# Input.net
KiCad netlist of a schematic drawn in Altium Designer
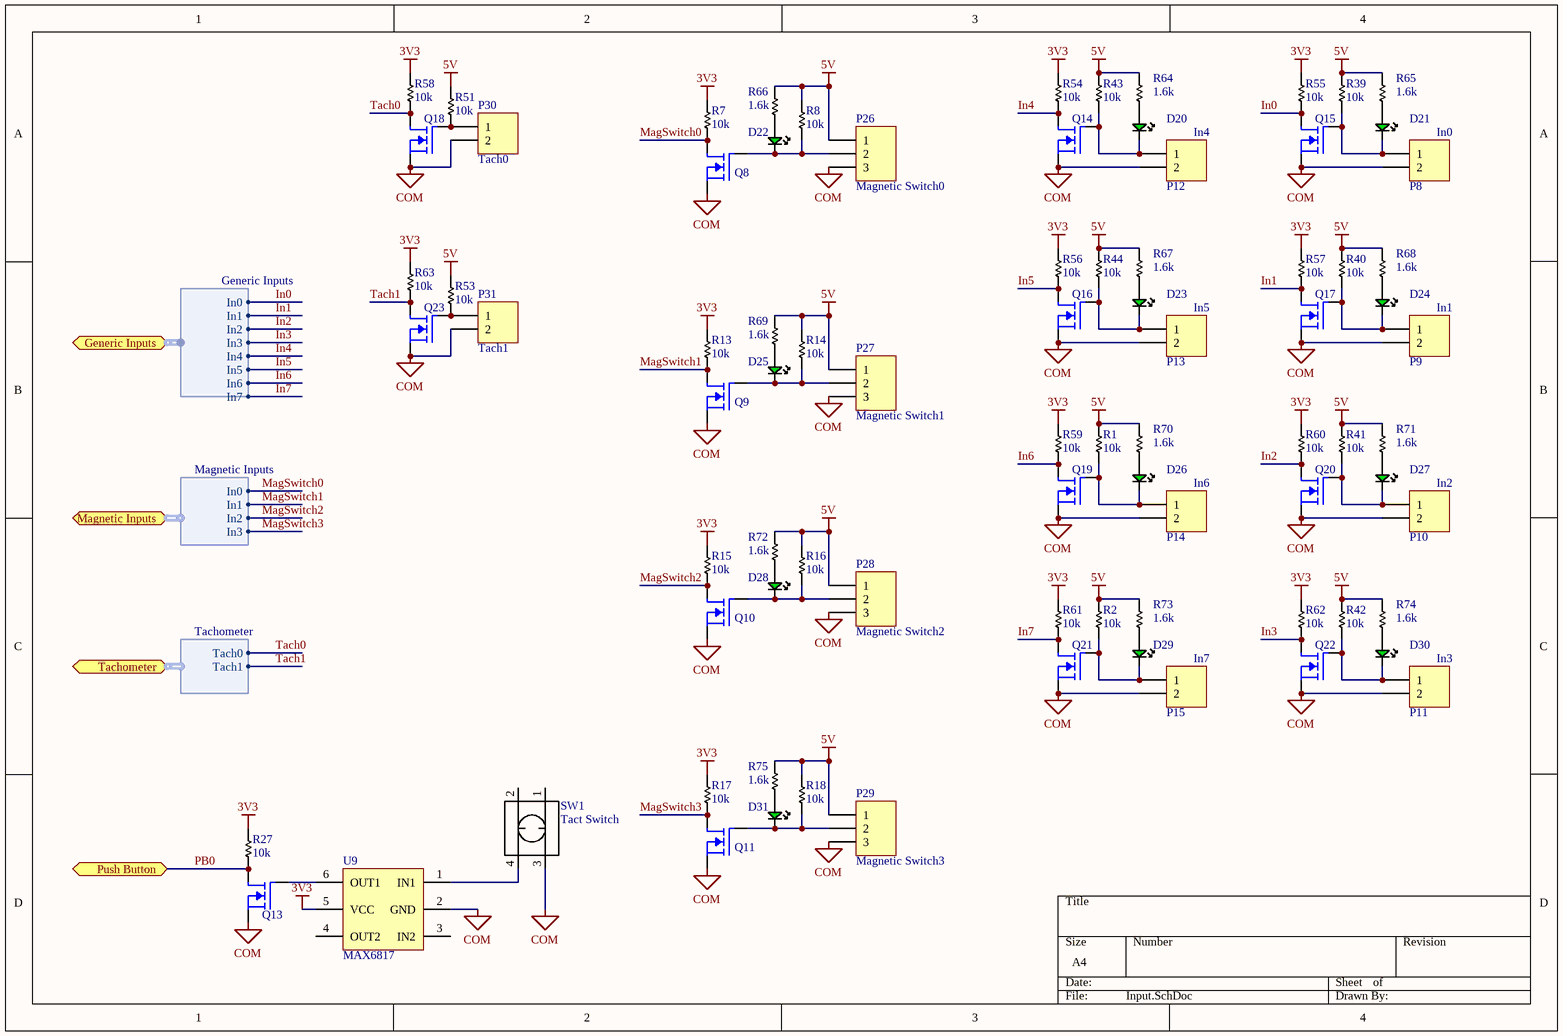
[diagram p0: Input.SchDoc]

(export (version "E")
  (design (tool "Eeschema 10.0.6"))
  (components
    (comp (ref "D20")
      (value "Green")
      (footprint "0603 - Led Green")
      (description "LED SMARTLED GREEN 570NM 0603")
      (fields
        (field (name "PART NUMBER") "LED-Green-2mA-lowBrigthness-0603")
        (field (name "MANUFACTURER") "OSRAM Opto Semiconductor")
        (field (name "CREATED BY") "Pier-Yves")
      )
      (libsource (lib "local") (part "Led Green"))
    )
    (comp (ref "D21")
      (value "Green")
      (footprint "0603 - Led Green")
      (description "LED SMARTLED GREEN 570NM 0603")
      (fields
        (field (name "PART NUMBER") "LED-Green-2mA-lowBrigthness-0603")
        (field (name "MANUFACTURER") "OSRAM Opto Semiconductor")
        (field (name "CREATED BY") "Pier-Yves")
      )
      (libsource (lib "local") (part "Led Green"))
    )
    (comp (ref "D22")
      (value "Green")
      (footprint "0603 - Led Green")
      (description "LED SMARTLED GREEN 570NM 0603")
      (fields
        (field (name "PART NUMBER") "LED-Green-2mA-lowBrigthness-0603")
        (field (name "MANUFACTURER") "OSRAM Opto Semiconductor")
        (field (name "CREATED BY") "Pier-Yves")
      )
      (libsource (lib "local") (part "Led Green"))
    )
    (comp (ref "D23")
      (value "Green")
      (footprint "0603 - Led Green")
      (description "LED SMARTLED GREEN 570NM 0603")
      (fields
        (field (name "PART NUMBER") "LED-Green-2mA-lowBrigthness-0603")
        (field (name "MANUFACTURER") "OSRAM Opto Semiconductor")
        (field (name "CREATED BY") "Pier-Yves")
      )
      (libsource (lib "local") (part "Led Green"))
    )
    (comp (ref "D24")
      (value "Green")
      (footprint "0603 - Led Green")
      (description "LED SMARTLED GREEN 570NM 0603")
      (fields
        (field (name "PART NUMBER") "LED-Green-2mA-lowBrigthness-0603")
        (field (name "MANUFACTURER") "OSRAM Opto Semiconductor")
        (field (name "CREATED BY") "Pier-Yves")
      )
      (libsource (lib "local") (part "Led Green"))
    )
    (comp (ref "D25")
      (value "Green")
      (footprint "0603 - Led Green")
      (description "LED SMARTLED GREEN 570NM 0603")
      (fields
        (field (name "PART NUMBER") "LED-Green-2mA-lowBrigthness-0603")
        (field (name "MANUFACTURER") "OSRAM Opto Semiconductor")
        (field (name "CREATED BY") "Pier-Yves")
      )
      (libsource (lib "local") (part "Led Green"))
    )
    (comp (ref "D26")
      (value "Green")
      (footprint "0603 - Led Green")
      (description "LED SMARTLED GREEN 570NM 0603")
      (fields
        (field (name "PART NUMBER") "LED-Green-2mA-lowBrigthness-0603")
        (field (name "MANUFACTURER") "OSRAM Opto Semiconductor")
        (field (name "CREATED BY") "Pier-Yves")
      )
      (libsource (lib "local") (part "Led Green"))
    )
    (comp (ref "D27")
      (value "Green")
      (footprint "0603 - Led Green")
      (description "LED SMARTLED GREEN 570NM 0603")
      (fields
        (field (name "PART NUMBER") "LED-Green-2mA-lowBrigthness-0603")
        (field (name "MANUFACTURER") "OSRAM Opto Semiconductor")
        (field (name "CREATED BY") "Pier-Yves")
      )
      (libsource (lib "local") (part "Led Green"))
    )
    (comp (ref "D28")
      (value "Green")
      (footprint "0603 - Led Green")
      (description "LED SMARTLED GREEN 570NM 0603")
      (fields
        (field (name "PART NUMBER") "LED-Green-2mA-lowBrigthness-0603")
        (field (name "MANUFACTURER") "OSRAM Opto Semiconductor")
        (field (name "CREATED BY") "Pier-Yves")
      )
      (libsource (lib "local") (part "Led Green"))
    )
    (comp (ref "D29")
      (value "Green")
      (footprint "0603 - Led Green")
      (description "LED SMARTLED GREEN 570NM 0603")
      (fields
        (field (name "PART NUMBER") "LED-Green-2mA-lowBrigthness-0603")
        (field (name "MANUFACTURER") "OSRAM Opto Semiconductor")
        (field (name "CREATED BY") "Pier-Yves")
      )
      (libsource (lib "local") (part "Led Green"))
    )
    (comp (ref "D30")
      (value "Green")
      (footprint "0603 - Led Green")
      (description "LED SMARTLED GREEN 570NM 0603")
      (fields
        (field (name "PART NUMBER") "LED-Green-2mA-lowBrigthness-0603")
        (field (name "MANUFACTURER") "OSRAM Opto Semiconductor")
        (field (name "CREATED BY") "Pier-Yves")
      )
      (libsource (lib "local") (part "Led Green"))
    )
    (comp (ref "D31")
      (value "Green")
      (footprint "0603 - Led Green")
      (description "LED SMARTLED GREEN 570NM 0603")
      (fields
        (field (name "PART NUMBER") "LED-Green-2mA-lowBrigthness-0603")
        (field (name "MANUFACTURER") "OSRAM Opto Semiconductor")
        (field (name "CREATED BY") "Pier-Yves")
      )
      (libsource (lib "local") (part "Led Green"))
    )
    (comp (ref "P8")
      (value "In0")
      (footprint "Headers - 1x2 - Vertical - Lock")
      (description "CONN HEADER 2POS .100\" STR TIN")
      (fields
        (field (name "PART NUMBER") "Header-0.100-Vertical-Lock-1X2")
        (field (name "MANUFACTURER") "Molex Inc")
        (field (name "PUBLISHER") "Altium Limited")
        (field (name "CREATED BY") "Pier-Yves")
      )
      (libsource (lib "local") (part "Header 1X2"))
    )
    (comp (ref "P9")
      (value "In1")
      (footprint "Headers - 1x2 - Vertical - Lock")
      (description "CONN HEADER 2POS .100\" STR TIN")
      (fields
        (field (name "PART NUMBER") "Header-0.100-Vertical-Lock-1X2")
        (field (name "MANUFACTURER") "Molex Inc")
        (field (name "PUBLISHER") "Altium Limited")
        (field (name "CREATED BY") "Pier-Yves")
      )
      (libsource (lib "local") (part "Header 1X2"))
    )
    (comp (ref "P10")
      (value "In2")
      (footprint "Headers - 1x2 - Vertical - Lock")
      (description "CONN HEADER 2POS .100\" STR TIN")
      (fields
        (field (name "PART NUMBER") "Header-0.100-Vertical-Lock-1X2")
        (field (name "MANUFACTURER") "Molex Inc")
        (field (name "PUBLISHER") "Altium Limited")
        (field (name "CREATED BY") "Pier-Yves")
      )
      (libsource (lib "local") (part "Header 1X2"))
    )
    (comp (ref "P11")
      (value "In3")
      (footprint "Headers - 1x2 - Vertical - Lock")
      (description "CONN HEADER 2POS .100\" STR TIN")
      (fields
        (field (name "PART NUMBER") "Header-0.100-Vertical-Lock-1X2")
        (field (name "MANUFACTURER") "Molex Inc")
        (field (name "PUBLISHER") "Altium Limited")
        (field (name "CREATED BY") "Pier-Yves")
      )
      (libsource (lib "local") (part "Header 1X2"))
    )
    (comp (ref "P12")
      (value "In4")
      (footprint "Headers - 1x2 - Vertical - Lock")
      (description "CONN HEADER 2POS .100\" STR TIN")
      (fields
        (field (name "PART NUMBER") "Header-0.100-Vertical-Lock-1X2")
        (field (name "MANUFACTURER") "Molex Inc")
        (field (name "PUBLISHER") "Altium Limited")
        (field (name "CREATED BY") "Pier-Yves")
      )
      (libsource (lib "local") (part "Header 1X2"))
    )
    (comp (ref "P13")
      (value "In5")
      (footprint "Headers - 1x2 - Vertical - Lock")
      (description "CONN HEADER 2POS .100\" STR TIN")
      (fields
        (field (name "PART NUMBER") "Header-0.100-Vertical-Lock-1X2")
        (field (name "MANUFACTURER") "Molex Inc")
        (field (name "PUBLISHER") "Altium Limited")
        (field (name "CREATED BY") "Pier-Yves")
      )
      (libsource (lib "local") (part "Header 1X2"))
    )
    (comp (ref "P14")
      (value "In6")
      (footprint "Headers - 1x2 - Vertical - Lock")
      (description "CONN HEADER 2POS .100\" STR TIN")
      (fields
        (field (name "PART NUMBER") "Header-0.100-Vertical-Lock-1X2")
        (field (name "MANUFACTURER") "Molex Inc")
        (field (name "PUBLISHER") "Altium Limited")
        (field (name "CREATED BY") "Pier-Yves")
      )
      (libsource (lib "local") (part "Header 1X2"))
    )
    (comp (ref "P15")
      (value "In7")
      (footprint "Headers - 1x2 - Vertical - Lock")
      (description "CONN HEADER 2POS .100\" STR TIN")
      (fields
        (field (name "PART NUMBER") "Header-0.100-Vertical-Lock-1X2")
        (field (name "MANUFACTURER") "Molex Inc")
        (field (name "PUBLISHER") "Altium Limited")
        (field (name "CREATED BY") "Pier-Yves")
      )
      (libsource (lib "local") (part "Header 1X2"))
    )
    (comp (ref "P26")
      (value "Magnetic Switch0")
      (footprint "Headers - 1x3 - Vertical - Lock")
      (description "CONN HEADER 3POS .100\" STR TIN")
      (fields
        (field (name "PART NUMBER") "Header-0.100-Vertical-Lock-1X3")
        (field (name "MANUFACTURER") "Molex Inc")
        (field (name "PUBLISHER") "Altium Limited")
        (field (name "CREATED BY") "Pier-Yves")
      )
      (libsource (lib "local") (part "Header 1X3"))
    )
    (comp (ref "P27")
      (value "Magnetic Switch1")
      (footprint "Headers - 1x3 - Vertical - Lock")
      (description "CONN HEADER 3POS .100\" STR TIN")
      (fields
        (field (name "PART NUMBER") "Header-0.100-Vertical-Lock-1X3")
        (field (name "MANUFACTURER") "Molex Inc")
        (field (name "PUBLISHER") "Altium Limited")
        (field (name "CREATED BY") "Pier-Yves")
      )
      (libsource (lib "local") (part "Header 1X3"))
    )
    (comp (ref "P28")
      (value "Magnetic Switch2")
      (footprint "Headers - 1x3 - Vertical - Lock")
      (description "CONN HEADER 3POS .100\" STR TIN")
      (fields
        (field (name "PART NUMBER") "Header-0.100-Vertical-Lock-1X3")
        (field (name "MANUFACTURER") "Molex Inc")
        (field (name "PUBLISHER") "Altium Limited")
        (field (name "CREATED BY") "Pier-Yves")
      )
      (libsource (lib "local") (part "Header 1X3"))
    )
    (comp (ref "P29")
      (value "Magnetic Switch3")
      (footprint "Headers - 1x3 - Vertical - Lock")
      (description "CONN HEADER 3POS .100\" STR TIN")
      (fields
        (field (name "PART NUMBER") "Header-0.100-Vertical-Lock-1X3")
        (field (name "MANUFACTURER") "Molex Inc")
        (field (name "PUBLISHER") "Altium Limited")
        (field (name "CREATED BY") "Pier-Yves")
      )
      (libsource (lib "local") (part "Header 1X3"))
    )
    (comp (ref "P30")
      (value "Tach0")
      (footprint "Headers - 1x2 - Vertical - Lock")
      (description "CONN HEADER 2POS .100\" STR TIN")
      (fields
        (field (name "PART NUMBER") "Header-0.100-Vertical-Lock-1X2")
        (field (name "MANUFACTURER") "Molex Inc")
        (field (name "PUBLISHER") "Altium Limited")
        (field (name "CREATED BY") "Pier-Yves")
      )
      (libsource (lib "local") (part "Header 1X2"))
    )
    (comp (ref "P31")
      (value "Tach1")
      (footprint "Headers - 1x2 - Vertical - Lock")
      (description "CONN HEADER 2POS .100\" STR TIN")
      (fields
        (field (name "PART NUMBER") "Header-0.100-Vertical-Lock-1X2")
        (field (name "MANUFACTURER") "Molex Inc")
        (field (name "PUBLISHER") "Altium Limited")
        (field (name "CREATED BY") "Pier-Yves")
      )
      (libsource (lib "local") (part "Header 1X2"))
    )
    (comp (ref "Q8")
      (value "MOSFET_N")
      (footprint "SOT23-3")
      (description "MosFET Channel-N SOT-23-3 3.3A")
      (fields
        (field (name "PART NUMBER") "2N7002")
        (field (name "MANUFACTURER") "Vishay Siliconix")
        (field (name "CREATED BY") "Pier-Yves")
      )
      (libsource (lib "local") (part "MOSFET_N_GSD"))
    )
    (comp (ref "Q9")
      (value "MOSFET_N")
      (footprint "SOT23-3")
      (description "MosFET Channel-N SOT-23-3 3.3A")
      (fields
        (field (name "PART NUMBER") "2N7002")
        (field (name "MANUFACTURER") "Vishay Siliconix")
        (field (name "CREATED BY") "Pier-Yves")
      )
      (libsource (lib "local") (part "MOSFET_N_GSD"))
    )
    (comp (ref "Q10")
      (value "MOSFET_N")
      (footprint "SOT23-3")
      (description "MosFET Channel-N SOT-23-3 3.3A")
      (fields
        (field (name "PART NUMBER") "2N7002")
        (field (name "MANUFACTURER") "Vishay Siliconix")
        (field (name "CREATED BY") "Pier-Yves")
      )
      (libsource (lib "local") (part "MOSFET_N_GSD"))
    )
    (comp (ref "Q11")
      (value "MOSFET_N")
      (footprint "SOT23-3")
      (description "MosFET Channel-N SOT-23-3 3.3A")
      (fields
        (field (name "PART NUMBER") "2N7002")
        (field (name "MANUFACTURER") "Vishay Siliconix")
        (field (name "CREATED BY") "Pier-Yves")
      )
      (libsource (lib "local") (part "MOSFET_N_GSD"))
    )
    (comp (ref "Q13")
      (value "MOSFET_N")
      (footprint "SOT23-3")
      (description "MosFET Channel-N SOT-23-3 3.3A")
      (fields
        (field (name "PART NUMBER") "2N7002")
        (field (name "MANUFACTURER") "Vishay Siliconix")
        (field (name "CREATED BY") "Pier-Yves")
      )
      (libsource (lib "local") (part "MOSFET_N_GSD"))
    )
    (comp (ref "Q14")
      (value "MOSFET_N")
      (footprint "SOT23-3")
      (description "MosFET Channel-N SOT-23-3 3.3A")
      (fields
        (field (name "PART NUMBER") "2N7002")
        (field (name "MANUFACTURER") "Vishay Siliconix")
        (field (name "CREATED BY") "Pier-Yves")
      )
      (libsource (lib "local") (part "MOSFET_N_GSD"))
    )
    (comp (ref "Q15")
      (value "MOSFET_N")
      (footprint "SOT23-3")
      (description "MosFET Channel-N SOT-23-3 3.3A")
      (fields
        (field (name "PART NUMBER") "2N7002")
        (field (name "MANUFACTURER") "Vishay Siliconix")
        (field (name "CREATED BY") "Pier-Yves")
      )
      (libsource (lib "local") (part "MOSFET_N_GSD"))
    )
    (comp (ref "Q16")
      (value "MOSFET_N")
      (footprint "SOT23-3")
      (description "MosFET Channel-N SOT-23-3 3.3A")
      (fields
        (field (name "PART NUMBER") "2N7002")
        (field (name "MANUFACTURER") "Vishay Siliconix")
        (field (name "CREATED BY") "Pier-Yves")
      )
      (libsource (lib "local") (part "MOSFET_N_GSD"))
    )
    (comp (ref "Q17")
      (value "MOSFET_N")
      (footprint "SOT23-3")
      (description "MosFET Channel-N SOT-23-3 3.3A")
      (fields
        (field (name "PART NUMBER") "2N7002")
        (field (name "MANUFACTURER") "Vishay Siliconix")
        (field (name "CREATED BY") "Pier-Yves")
      )
      (libsource (lib "local") (part "MOSFET_N_GSD"))
    )
    (comp (ref "Q18")
      (value "MOSFET_N")
      (footprint "SOT23-3")
      (description "MosFET Channel-N SOT-23-3 3.3A")
      (fields
        (field (name "PART NUMBER") "2N7002")
        (field (name "MANUFACTURER") "Vishay Siliconix")
        (field (name "CREATED BY") "Pier-Yves")
      )
      (libsource (lib "local") (part "MOSFET_N_GSD"))
    )
    (comp (ref "Q19")
      (value "MOSFET_N")
      (footprint "SOT23-3")
      (description "MosFET Channel-N SOT-23-3 3.3A")
      (fields
        (field (name "PART NUMBER") "2N7002")
        (field (name "MANUFACTURER") "Vishay Siliconix")
        (field (name "CREATED BY") "Pier-Yves")
      )
      (libsource (lib "local") (part "MOSFET_N_GSD"))
    )
    (comp (ref "Q20")
      (value "MOSFET_N")
      (footprint "SOT23-3")
      (description "MosFET Channel-N SOT-23-3 3.3A")
      (fields
        (field (name "PART NUMBER") "2N7002")
        (field (name "MANUFACTURER") "Vishay Siliconix")
        (field (name "CREATED BY") "Pier-Yves")
      )
      (libsource (lib "local") (part "MOSFET_N_GSD"))
    )
    (comp (ref "Q21")
      (value "MOSFET_N")
      (footprint "SOT23-3")
      (description "MosFET Channel-N SOT-23-3 3.3A")
      (fields
        (field (name "PART NUMBER") "2N7002")
        (field (name "MANUFACTURER") "Vishay Siliconix")
        (field (name "CREATED BY") "Pier-Yves")
      )
      (libsource (lib "local") (part "MOSFET_N_GSD"))
    )
    (comp (ref "Q22")
      (value "MOSFET_N")
      (footprint "SOT23-3")
      (description "MosFET Channel-N SOT-23-3 3.3A")
      (fields
        (field (name "PART NUMBER") "2N7002")
        (field (name "MANUFACTURER") "Vishay Siliconix")
        (field (name "CREATED BY") "Pier-Yves")
      )
      (libsource (lib "local") (part "MOSFET_N_GSD"))
    )
    (comp (ref "Q23")
      (value "MOSFET_N")
      (footprint "SOT23-3")
      (description "MosFET Channel-N SOT-23-3 3.3A")
      (fields
        (field (name "PART NUMBER") "2N7002")
        (field (name "MANUFACTURER") "Vishay Siliconix")
        (field (name "CREATED BY") "Pier-Yves")
      )
      (libsource (lib "local") (part "MOSFET_N_GSD"))
    )
    (comp (ref "R1")
      (value "10k")
      (footprint "0805 - Resistor")
      (description "RES 10K OHM 1/8W 5% 0805 SMD")
      (fields
        (field (name "PART NUMBER") "Yagao-RC0805-10k")
        (field (name "MANUFACTURER") "Yagao")
        (field (name "CREATED BY") "Pier-Yves")
      )
      (libsource (lib "local") (part "Res"))
    )
    (comp (ref "R2")
      (value "10k")
      (footprint "0805 - Resistor")
      (description "RES 10K OHM 1/8W 5% 0805 SMD")
      (fields
        (field (name "PART NUMBER") "Yagao-RC0805-10k")
        (field (name "MANUFACTURER") "Yagao")
        (field (name "CREATED BY") "Pier-Yves")
      )
      (libsource (lib "local") (part "Res"))
    )
    (comp (ref "R7")
      (value "10k")
      (footprint "0805 - Resistor")
      (description "RES 10K OHM 1/8W 5% 0805 SMD")
      (fields
        (field (name "PART NUMBER") "Yagao-RC0805-10k")
        (field (name "MANUFACTURER") "Yagao")
        (field (name "CREATED BY") "Pier-Yves")
      )
      (libsource (lib "local") (part "Res"))
    )
    (comp (ref "R8")
      (value "10k")
      (footprint "0805 - Resistor")
      (description "RES 10K OHM 1/8W 5% 0805 SMD")
      (fields
        (field (name "PART NUMBER") "Yagao-RC0805-10k")
        (field (name "MANUFACTURER") "Yagao")
        (field (name "CREATED BY") "Pier-Yves")
      )
      (libsource (lib "local") (part "Res"))
    )
    (comp (ref "R13")
      (value "10k")
      (footprint "0805 - Resistor")
      (description "RES 10K OHM 1/8W 5% 0805 SMD")
      (fields
        (field (name "PART NUMBER") "Yagao-RC0805-10k")
        (field (name "MANUFACTURER") "Yagao")
        (field (name "CREATED BY") "Pier-Yves")
      )
      (libsource (lib "local") (part "Res"))
    )
    (comp (ref "R14")
      (value "10k")
      (footprint "0805 - Resistor")
      (description "RES 10K OHM 1/8W 5% 0805 SMD")
      (fields
        (field (name "PART NUMBER") "Yagao-RC0805-10k")
        (field (name "MANUFACTURER") "Yagao")
        (field (name "CREATED BY") "Pier-Yves")
      )
      (libsource (lib "local") (part "Res"))
    )
    (comp (ref "R15")
      (value "10k")
      (footprint "0805 - Resistor")
      (description "RES 10K OHM 1/8W 5% 0805 SMD")
      (fields
        (field (name "PART NUMBER") "Yagao-RC0805-10k")
        (field (name "MANUFACTURER") "Yagao")
        (field (name "CREATED BY") "Pier-Yves")
      )
      (libsource (lib "local") (part "Res"))
    )
    (comp (ref "R16")
      (value "10k")
      (footprint "0805 - Resistor")
      (description "RES 10K OHM 1/8W 5% 0805 SMD")
      (fields
        (field (name "PART NUMBER") "Yagao-RC0805-10k")
        (field (name "MANUFACTURER") "Yagao")
        (field (name "CREATED BY") "Pier-Yves")
      )
      (libsource (lib "local") (part "Res"))
    )
    (comp (ref "R17")
      (value "10k")
      (footprint "0805 - Resistor")
      (description "RES 10K OHM 1/8W 5% 0805 SMD")
      (fields
        (field (name "PART NUMBER") "Yagao-RC0805-10k")
        (field (name "MANUFACTURER") "Yagao")
        (field (name "CREATED BY") "Pier-Yves")
      )
      (libsource (lib "local") (part "Res"))
    )
    (comp (ref "R18")
      (value "10k")
      (footprint "0805 - Resistor")
      (description "RES 10K OHM 1/8W 5% 0805 SMD")
      (fields
        (field (name "PART NUMBER") "Yagao-RC0805-10k")
        (field (name "MANUFACTURER") "Yagao")
        (field (name "CREATED BY") "Pier-Yves")
      )
      (libsource (lib "local") (part "Res"))
    )
    (comp (ref "R27")
      (value "10k")
      (footprint "0805 - Resistor")
      (description "RES 10K OHM 1/8W 5% 0805 SMD")
      (fields
        (field (name "PART NUMBER") "Yagao-RC0805-10k")
        (field (name "MANUFACTURER") "Yagao")
        (field (name "CREATED BY") "Pier-Yves")
      )
      (libsource (lib "local") (part "Res"))
    )
    (comp (ref "R39")
      (value "10k")
      (footprint "0805 - Resistor")
      (description "RES 10K OHM 1/8W 5% 0805 SMD")
      (fields
        (field (name "PART NUMBER") "Yagao-RC0805-10k")
        (field (name "MANUFACTURER") "Yagao")
        (field (name "CREATED BY") "Pier-Yves")
      )
      (libsource (lib "local") (part "Res"))
    )
    (comp (ref "R40")
      (value "10k")
      (footprint "0805 - Resistor")
      (description "RES 10K OHM 1/8W 5% 0805 SMD")
      (fields
        (field (name "PART NUMBER") "Yagao-RC0805-10k")
        (field (name "MANUFACTURER") "Yagao")
        (field (name "CREATED BY") "Pier-Yves")
      )
      (libsource (lib "local") (part "Res"))
    )
    (comp (ref "R41")
      (value "10k")
      (footprint "0805 - Resistor")
      (description "RES 10K OHM 1/8W 5% 0805 SMD")
      (fields
        (field (name "PART NUMBER") "Yagao-RC0805-10k")
        (field (name "MANUFACTURER") "Yagao")
        (field (name "CREATED BY") "Pier-Yves")
      )
      (libsource (lib "local") (part "Res"))
    )
    (comp (ref "R42")
      (value "10k")
      (footprint "0805 - Resistor")
      (description "RES 10K OHM 1/8W 5% 0805 SMD")
      (fields
        (field (name "PART NUMBER") "Yagao-RC0805-10k")
        (field (name "MANUFACTURER") "Yagao")
        (field (name "CREATED BY") "Pier-Yves")
      )
      (libsource (lib "local") (part "Res"))
    )
    (comp (ref "R43")
      (value "10k")
      (footprint "0805 - Resistor")
      (description "RES 10K OHM 1/8W 5% 0805 SMD")
      (fields
        (field (name "PART NUMBER") "Yagao-RC0805-10k")
        (field (name "MANUFACTURER") "Yagao")
        (field (name "CREATED BY") "Pier-Yves")
      )
      (libsource (lib "local") (part "Res"))
    )
    (comp (ref "R44")
      (value "10k")
      (footprint "0805 - Resistor")
      (description "RES 10K OHM 1/8W 5% 0805 SMD")
      (fields
        (field (name "PART NUMBER") "Yagao-RC0805-10k")
        (field (name "MANUFACTURER") "Yagao")
        (field (name "CREATED BY") "Pier-Yves")
      )
      (libsource (lib "local") (part "Res"))
    )
    (comp (ref "R51")
      (value "10k")
      (footprint "0805 - Resistor")
      (description "RES 10K OHM 1/8W 5% 0805 SMD")
      (fields
        (field (name "PART NUMBER") "Yagao-RC0805-10k")
        (field (name "MANUFACTURER") "Yagao")
        (field (name "CREATED BY") "Pier-Yves")
      )
      (libsource (lib "local") (part "Res"))
    )
    (comp (ref "R53")
      (value "10k")
      (footprint "0805 - Resistor")
      (description "RES 10K OHM 1/8W 5% 0805 SMD")
      (fields
        (field (name "PART NUMBER") "Yagao-RC0805-10k")
        (field (name "MANUFACTURER") "Yagao")
        (field (name "CREATED BY") "Pier-Yves")
      )
      (libsource (lib "local") (part "Res"))
    )
    (comp (ref "R54")
      (value "10k")
      (footprint "0805 - Resistor")
      (description "RES 10K OHM 1/8W 5% 0805 SMD")
      (fields
        (field (name "PART NUMBER") "Yagao-RC0805-10k")
        (field (name "MANUFACTURER") "Yagao")
        (field (name "CREATED BY") "Pier-Yves")
      )
      (libsource (lib "local") (part "Res"))
    )
    (comp (ref "R55")
      (value "10k")
      (footprint "0805 - Resistor")
      (description "RES 10K OHM 1/8W 5% 0805 SMD")
      (fields
        (field (name "PART NUMBER") "Yagao-RC0805-10k")
        (field (name "MANUFACTURER") "Yagao")
        (field (name "CREATED BY") "Pier-Yves")
      )
      (libsource (lib "local") (part "Res"))
    )
    (comp (ref "R56")
      (value "10k")
      (footprint "0805 - Resistor")
      (description "RES 10K OHM 1/8W 5% 0805 SMD")
      (fields
        (field (name "PART NUMBER") "Yagao-RC0805-10k")
        (field (name "MANUFACTURER") "Yagao")
        (field (name "CREATED BY") "Pier-Yves")
      )
      (libsource (lib "local") (part "Res"))
    )
    (comp (ref "R57")
      (value "10k")
      (footprint "0805 - Resistor")
      (description "RES 10K OHM 1/8W 5% 0805 SMD")
      (fields
        (field (name "PART NUMBER") "Yagao-RC0805-10k")
        (field (name "MANUFACTURER") "Yagao")
        (field (name "CREATED BY") "Pier-Yves")
      )
      (libsource (lib "local") (part "Res"))
    )
    (comp (ref "R58")
      (value "10k")
      (footprint "0805 - Resistor")
      (description "RES 10K OHM 1/8W 5% 0805 SMD")
      (fields
        (field (name "PART NUMBER") "Yagao-RC0805-10k")
        (field (name "MANUFACTURER") "Yagao")
        (field (name "CREATED BY") "Pier-Yves")
      )
      (libsource (lib "local") (part "Res"))
    )
    (comp (ref "R59")
      (value "10k")
      (footprint "0805 - Resistor")
      (description "RES 10K OHM 1/8W 5% 0805 SMD")
      (fields
        (field (name "PART NUMBER") "Yagao-RC0805-10k")
        (field (name "MANUFACTURER") "Yagao")
        (field (name "CREATED BY") "Pier-Yves")
      )
      (libsource (lib "local") (part "Res"))
    )
    (comp (ref "R60")
      (value "10k")
      (footprint "0805 - Resistor")
      (description "RES 10K OHM 1/8W 5% 0805 SMD")
      (fields
        (field (name "PART NUMBER") "Yagao-RC0805-10k")
        (field (name "MANUFACTURER") "Yagao")
        (field (name "CREATED BY") "Pier-Yves")
      )
      (libsource (lib "local") (part "Res"))
    )
    (comp (ref "R61")
      (value "10k")
      (footprint "0805 - Resistor")
      (description "RES 10K OHM 1/8W 5% 0805 SMD")
      (fields
        (field (name "PART NUMBER") "Yagao-RC0805-10k")
        (field (name "MANUFACTURER") "Yagao")
        (field (name "CREATED BY") "Pier-Yves")
      )
      (libsource (lib "local") (part "Res"))
    )
    (comp (ref "R62")
      (value "10k")
      (footprint "0805 - Resistor")
      (description "RES 10K OHM 1/8W 5% 0805 SMD")
      (fields
        (field (name "PART NUMBER") "Yagao-RC0805-10k")
        (field (name "MANUFACTURER") "Yagao")
        (field (name "CREATED BY") "Pier-Yves")
      )
      (libsource (lib "local") (part "Res"))
    )
    (comp (ref "R63")
      (value "10k")
      (footprint "0805 - Resistor")
      (description "RES 10K OHM 1/8W 5% 0805 SMD")
      (fields
        (field (name "PART NUMBER") "Yagao-RC0805-10k")
        (field (name "MANUFACTURER") "Yagao")
        (field (name "CREATED BY") "Pier-Yves")
      )
      (libsource (lib "local") (part "Res"))
    )
    (comp (ref "R64")
      (value "1.6k")
      (footprint "0805 - Resistor")
      (description "RES 1.6K OHM 1/8W 5% 0805 SMD")
      (fields
        (field (name "PART NUMBER") "Yagao-RC0805-1.6k")
        (field (name "MANUFACTURER") "Yagao")
        (field (name "CREATED BY") "Pier-Yves")
      )
      (libsource (lib "local") (part "Res"))
    )
    (comp (ref "R65")
      (value "1.6k")
      (footprint "0805 - Resistor")
      (description "RES 1.6K OHM 1/8W 5% 0805 SMD")
      (fields
        (field (name "PART NUMBER") "Yagao-RC0805-1.6k")
        (field (name "MANUFACTURER") "Yagao")
        (field (name "CREATED BY") "Pier-Yves")
      )
      (libsource (lib "local") (part "Res"))
    )
    (comp (ref "R66")
      (value "1.6k")
      (footprint "0805 - Resistor")
      (description "RES 1.6K OHM 1/8W 5% 0805 SMD")
      (fields
        (field (name "PART NUMBER") "Yagao-RC0805-1.6k")
        (field (name "MANUFACTURER") "Yagao")
        (field (name "CREATED BY") "Pier-Yves")
      )
      (libsource (lib "local") (part "Res"))
    )
    (comp (ref "R67")
      (value "1.6k")
      (footprint "0805 - Resistor")
      (description "RES 1.6K OHM 1/8W 5% 0805 SMD")
      (fields
        (field (name "PART NUMBER") "Yagao-RC0805-1.6k")
        (field (name "MANUFACTURER") "Yagao")
        (field (name "CREATED BY") "Pier-Yves")
      )
      (libsource (lib "local") (part "Res"))
    )
    (comp (ref "R68")
      (value "1.6k")
      (footprint "0805 - Resistor")
      (description "RES 1.6K OHM 1/8W 5% 0805 SMD")
      (fields
        (field (name "PART NUMBER") "Yagao-RC0805-1.6k")
        (field (name "MANUFACTURER") "Yagao")
        (field (name "CREATED BY") "Pier-Yves")
      )
      (libsource (lib "local") (part "Res"))
    )
    (comp (ref "R69")
      (value "1.6k")
      (footprint "0805 - Resistor")
      (description "RES 1.6K OHM 1/8W 5% 0805 SMD")
      (fields
        (field (name "PART NUMBER") "Yagao-RC0805-1.6k")
        (field (name "MANUFACTURER") "Yagao")
        (field (name "CREATED BY") "Pier-Yves")
      )
      (libsource (lib "local") (part "Res"))
    )
    (comp (ref "R70")
      (value "1.6k")
      (footprint "0805 - Resistor")
      (description "RES 1.6K OHM 1/8W 5% 0805 SMD")
      (fields
        (field (name "PART NUMBER") "Yagao-RC0805-1.6k")
        (field (name "MANUFACTURER") "Yagao")
        (field (name "CREATED BY") "Pier-Yves")
      )
      (libsource (lib "local") (part "Res"))
    )
    (comp (ref "R71")
      (value "1.6k")
      (footprint "0805 - Resistor")
      (description "RES 1.6K OHM 1/8W 5% 0805 SMD")
      (fields
        (field (name "PART NUMBER") "Yagao-RC0805-1.6k")
        (field (name "MANUFACTURER") "Yagao")
        (field (name "CREATED BY") "Pier-Yves")
      )
      (libsource (lib "local") (part "Res"))
    )
    (comp (ref "R72")
      (value "1.6k")
      (footprint "0805 - Resistor")
      (description "RES 1.6K OHM 1/8W 5% 0805 SMD")
      (fields
        (field (name "PART NUMBER") "Yagao-RC0805-1.6k")
        (field (name "MANUFACTURER") "Yagao")
        (field (name "CREATED BY") "Pier-Yves")
      )
      (libsource (lib "local") (part "Res"))
    )
    (comp (ref "R73")
      (value "1.6k")
      (footprint "0805 - Resistor")
      (description "RES 1.6K OHM 1/8W 5% 0805 SMD")
      (fields
        (field (name "PART NUMBER") "Yagao-RC0805-1.6k")
        (field (name "MANUFACTURER") "Yagao")
        (field (name "CREATED BY") "Pier-Yves")
      )
      (libsource (lib "local") (part "Res"))
    )
    (comp (ref "R74")
      (value "1.6k")
      (footprint "0805 - Resistor")
      (description "RES 1.6K OHM 1/8W 5% 0805 SMD")
      (fields
        (field (name "PART NUMBER") "Yagao-RC0805-1.6k")
        (field (name "MANUFACTURER") "Yagao")
        (field (name "CREATED BY") "Pier-Yves")
      )
      (libsource (lib "local") (part "Res"))
    )
    (comp (ref "R75")
      (value "1.6k")
      (footprint "0805 - Resistor")
      (description "RES 1.6K OHM 1/8W 5% 0805 SMD")
      (fields
        (field (name "PART NUMBER") "Yagao-RC0805-1.6k")
        (field (name "MANUFACTURER") "Yagao")
        (field (name "CREATED BY") "Pier-Yves")
      )
      (libsource (lib "local") (part "Res"))
    )
    (comp (ref "SW1")
      (value "Tact Switch")
      (footprint "TE FSMJSMA")
      (description "SWITCH TACTILE SPST-NO 0.05A 12V")
      (fields
        (field (name "PART NUMBER") "TactSwitch-SMD-Vertical-GullWing-6x6")
        (field (name "MANUFACTURER") "TE Connectivity")
        (field (name "CREATED BY") "Pier-Yves")
      )
      (libsource (lib "local") (part "Tact Switch"))
    )
    (comp (ref "U9")
      (value "MAX6817")
      (footprint "SOT23-6")
      (description "IC DEBOUNCER SWITCH DUAL SOT23-6")
      (fields (field (name "MANUFACTURER") "Maxim Integrated") (field (name "CREATED BY") "Pier-Yves"))
      (libsource (lib "local") (part "MAX6817"))
    )
  )
  (nets
    (net (code "5") (name "/In0") (class "Default")
      (node (ref "Q15") (pin "3") (pinfunction "D_3") (pintype "passive"))
      (node (ref "R55") (pin "1") (pinfunction "1_1") (pintype "passive"))
    )
    (net (code "6") (name "/In1") (class "Default")
      (node (ref "Q17") (pin "3") (pinfunction "D_3") (pintype "passive"))
      (node (ref "R57") (pin "1") (pinfunction "1_1") (pintype "passive"))
    )
    (net (code "7") (name "/In2") (class "Default")
      (node (ref "Q20") (pin "3") (pinfunction "D_3") (pintype "passive"))
      (node (ref "R60") (pin "1") (pinfunction "1_1") (pintype "passive"))
    )
    (net (code "8") (name "/In3") (class "Default")
      (node (ref "Q22") (pin "3") (pinfunction "D_3") (pintype "passive"))
      (node (ref "R62") (pin "1") (pinfunction "1_1") (pintype "passive"))
    )
    (net (code "9") (name "/In4") (class "Default")
      (node (ref "Q14") (pin "3") (pinfunction "D_3") (pintype "passive"))
      (node (ref "R54") (pin "1") (pinfunction "1_1") (pintype "passive"))
    )
    (net (code "10") (name "/In5") (class "Default")
      (node (ref "Q16") (pin "3") (pinfunction "D_3") (pintype "passive"))
      (node (ref "R56") (pin "1") (pinfunction "1_1") (pintype "passive"))
    )
    (net (code "11") (name "/In6") (class "Default")
      (node (ref "Q19") (pin "3") (pinfunction "D_3") (pintype "passive"))
      (node (ref "R59") (pin "1") (pinfunction "1_1") (pintype "passive"))
    )
    (net (code "12") (name "/In7") (class "Default")
      (node (ref "Q21") (pin "3") (pinfunction "D_3") (pintype "passive"))
      (node (ref "R61") (pin "1") (pinfunction "1_1") (pintype "passive"))
    )
    (net (code "13") (name "/MagSwitch0") (class "Default")
      (node (ref "Q8") (pin "3") (pinfunction "D_3") (pintype "passive"))
      (node (ref "R7") (pin "1") (pinfunction "1_1") (pintype "passive"))
    )
    (net (code "14") (name "/MagSwitch1") (class "Default")
      (node (ref "Q9") (pin "3") (pinfunction "D_3") (pintype "passive"))
      (node (ref "R13") (pin "1") (pinfunction "1_1") (pintype "passive"))
    )
    (net (code "15") (name "/MagSwitch2") (class "Default")
      (node (ref "Q10") (pin "3") (pinfunction "D_3") (pintype "passive"))
      (node (ref "R15") (pin "1") (pinfunction "1_1") (pintype "passive"))
    )
    (net (code "16") (name "/MagSwitch3") (class "Default")
      (node (ref "Q11") (pin "3") (pinfunction "D_3") (pintype "passive"))
      (node (ref "R17") (pin "1") (pinfunction "1_1") (pintype "passive"))
    )
    (net (code "17") (name "/PB0") (class "Default")
      (node (ref "Q13") (pin "3") (pinfunction "D_3") (pintype "passive"))
      (node (ref "R27") (pin "1") (pinfunction "1_1") (pintype "passive"))
    )
    (net (code "18") (name "/Tach0") (class "Default")
      (node (ref "Q18") (pin "3") (pinfunction "D_3") (pintype "passive"))
      (node (ref "R58") (pin "1") (pinfunction "1_1") (pintype "passive"))
    )
    (net (code "19") (name "/Tach1") (class "Default")
      (node (ref "Q23") (pin "3") (pinfunction "D_3") (pintype "passive"))
      (node (ref "R63") (pin "1") (pinfunction "1_1") (pintype "passive"))
    )
    (net (code "23") (name "3V3") (class "Default")
      (node (ref "R13") (pin "2") (pinfunction "2_2") (pintype "passive"))
      (node (ref "R15") (pin "2") (pinfunction "2_2") (pintype "passive"))
      (node (ref "R17") (pin "2") (pinfunction "2_2") (pintype "passive"))
      (node (ref "R27") (pin "2") (pinfunction "2_2") (pintype "passive"))
      (node (ref "R54") (pin "2") (pinfunction "2_2") (pintype "passive"))
      (node (ref "R55") (pin "2") (pinfunction "2_2") (pintype "passive"))
      (node (ref "R56") (pin "2") (pinfunction "2_2") (pintype "passive"))
      (node (ref "R57") (pin "2") (pinfunction "2_2") (pintype "passive"))
      (node (ref "R58") (pin "2") (pinfunction "2_2") (pintype "passive"))
      (node (ref "R59") (pin "2") (pinfunction "2_2") (pintype "passive"))
      (node (ref "R60") (pin "2") (pinfunction "2_2") (pintype "passive"))
      (node (ref "R61") (pin "2") (pinfunction "2_2") (pintype "passive"))
      (node (ref "R62") (pin "2") (pinfunction "2_2") (pintype "passive"))
      (node (ref "R63") (pin "2") (pinfunction "2_2") (pintype "passive"))
      (node (ref "R7") (pin "2") (pinfunction "2_2") (pintype "passive"))
      (node (ref "U9") (pin "5") (pinfunction "VCC_5") (pintype "passive"))
    )
    (net (code "24") (name "5V") (class "Default")
      (node (ref "P26") (pin "1") (pinfunction "1_1") (pintype "passive"))
      (node (ref "P27") (pin "1") (pinfunction "1_1") (pintype "passive"))
      (node (ref "P28") (pin "1") (pinfunction "1_1") (pintype "passive"))
      (node (ref "P29") (pin "1") (pinfunction "1_1") (pintype "passive"))
      (node (ref "R1") (pin "2") (pinfunction "2_2") (pintype "passive"))
      (node (ref "R14") (pin "2") (pinfunction "2_2") (pintype "passive"))
      (node (ref "R16") (pin "2") (pinfunction "2_2") (pintype "passive"))
      (node (ref "R18") (pin "2") (pinfunction "2_2") (pintype "passive"))
      (node (ref "R2") (pin "2") (pinfunction "2_2") (pintype "passive"))
      (node (ref "R39") (pin "2") (pinfunction "2_2") (pintype "passive"))
      (node (ref "R40") (pin "2") (pinfunction "2_2") (pintype "passive"))
      (node (ref "R41") (pin "2") (pinfunction "2_2") (pintype "passive"))
      (node (ref "R42") (pin "2") (pinfunction "2_2") (pintype "passive"))
      (node (ref "R43") (pin "2") (pinfunction "2_2") (pintype "passive"))
      (node (ref "R44") (pin "2") (pinfunction "2_2") (pintype "passive"))
      (node (ref "R51") (pin "2") (pinfunction "2_2") (pintype "passive"))
      (node (ref "R53") (pin "2") (pinfunction "2_2") (pintype "passive"))
      (node (ref "R64") (pin "2") (pinfunction "2_2") (pintype "passive"))
      (node (ref "R65") (pin "2") (pinfunction "2_2") (pintype "passive"))
      (node (ref "R66") (pin "2") (pinfunction "2_2") (pintype "passive"))
      (node (ref "R67") (pin "2") (pinfunction "2_2") (pintype "passive"))
      (node (ref "R68") (pin "2") (pinfunction "2_2") (pintype "passive"))
      (node (ref "R69") (pin "2") (pinfunction "2_2") (pintype "passive"))
      (node (ref "R70") (pin "2") (pinfunction "2_2") (pintype "passive"))
      (node (ref "R71") (pin "2") (pinfunction "2_2") (pintype "passive"))
      (node (ref "R72") (pin "2") (pinfunction "2_2") (pintype "passive"))
      (node (ref "R73") (pin "2") (pinfunction "2_2") (pintype "passive"))
      (node (ref "R74") (pin "2") (pinfunction "2_2") (pintype "passive"))
      (node (ref "R75") (pin "2") (pinfunction "2_2") (pintype "passive"))
      (node (ref "R8") (pin "2") (pinfunction "2_2") (pintype "passive"))
    )
    (net (code "25") (name "COM") (class "Default")
      (node (ref "P10") (pin "2") (pinfunction "2_2") (pintype "passive"))
      (node (ref "P11") (pin "2") (pinfunction "2_2") (pintype "passive"))
      (node (ref "P12") (pin "2") (pinfunction "2_2") (pintype "passive"))
      (node (ref "P13") (pin "2") (pinfunction "2_2") (pintype "passive"))
      (node (ref "P14") (pin "2") (pinfunction "2_2") (pintype "passive"))
      (node (ref "P15") (pin "2") (pinfunction "2_2") (pintype "passive"))
      (node (ref "P26") (pin "3") (pinfunction "3_3") (pintype "passive"))
      (node (ref "P27") (pin "3") (pinfunction "3_3") (pintype "passive"))
      (node (ref "P28") (pin "3") (pinfunction "3_3") (pintype "passive"))
      (node (ref "P29") (pin "3") (pinfunction "3_3") (pintype "passive"))
      (node (ref "P30") (pin "2") (pinfunction "2_2") (pintype "passive"))
      (node (ref "P31") (pin "2") (pinfunction "2_2") (pintype "passive"))
      (node (ref "P8") (pin "2") (pinfunction "2_2") (pintype "passive"))
      (node (ref "P9") (pin "2") (pinfunction "2_2") (pintype "passive"))
      (node (ref "Q10") (pin "2") (pinfunction "S_2") (pintype "passive"))
      (node (ref "Q11") (pin "2") (pinfunction "S_2") (pintype "passive"))
      (node (ref "Q13") (pin "2") (pinfunction "S_2") (pintype "passive"))
      (node (ref "Q14") (pin "2") (pinfunction "S_2") (pintype "passive"))
      (node (ref "Q15") (pin "2") (pinfunction "S_2") (pintype "passive"))
      (node (ref "Q16") (pin "2") (pinfunction "S_2") (pintype "passive"))
      (node (ref "Q17") (pin "2") (pinfunction "S_2") (pintype "passive"))
      (node (ref "Q18") (pin "2") (pinfunction "S_2") (pintype "passive"))
      (node (ref "Q19") (pin "2") (pinfunction "S_2") (pintype "passive"))
      (node (ref "Q20") (pin "2") (pinfunction "S_2") (pintype "passive"))
      (node (ref "Q21") (pin "2") (pinfunction "S_2") (pintype "passive"))
      (node (ref "Q22") (pin "2") (pinfunction "S_2") (pintype "passive"))
      (node (ref "Q23") (pin "2") (pinfunction "S_2") (pintype "passive"))
      (node (ref "Q8") (pin "2") (pinfunction "S_2") (pintype "passive"))
      (node (ref "Q9") (pin "2") (pinfunction "S_2") (pintype "passive"))
      (node (ref "SW1") (pin "3") (pinfunction "3_3") (pintype "passive"))
      (node (ref "U9") (pin "2") (pinfunction "GND_2") (pintype "passive"))
    )
    (net (code "26") (name "Net-(D20-A)") (class "Default")
      (node (ref "D20") (pin "1") (pinfunction "A_1") (pintype "passive"))
      (node (ref "R64") (pin "1") (pinfunction "1_1") (pintype "passive"))
    )
    (net (code "27") (name "Net-(D20-K)") (class "Default")
      (node (ref "D20") (pin "2") (pinfunction "K_2") (pintype "passive"))
      (node (ref "P12") (pin "1") (pinfunction "1_1") (pintype "passive"))
      (node (ref "Q14") (pin "1") (pinfunction "G_1") (pintype "passive"))
      (node (ref "R43") (pin "1") (pinfunction "1_1") (pintype "passive"))
    )
    (net (code "28") (name "Net-(D21-A)") (class "Default")
      (node (ref "D21") (pin "1") (pinfunction "A_1") (pintype "passive"))
      (node (ref "R65") (pin "1") (pinfunction "1_1") (pintype "passive"))
    )
    (net (code "29") (name "Net-(D21-K)") (class "Default")
      (node (ref "D21") (pin "2") (pinfunction "K_2") (pintype "passive"))
      (node (ref "P8") (pin "1") (pinfunction "1_1") (pintype "passive"))
      (node (ref "Q15") (pin "1") (pinfunction "G_1") (pintype "passive"))
      (node (ref "R39") (pin "1") (pinfunction "1_1") (pintype "passive"))
    )
    (net (code "30") (name "Net-(D22-A)") (class "Default")
      (node (ref "D22") (pin "1") (pinfunction "A_1") (pintype "passive"))
      (node (ref "R66") (pin "1") (pinfunction "1_1") (pintype "passive"))
    )
    (net (code "31") (name "Net-(D22-K)") (class "Default")
      (node (ref "D22") (pin "2") (pinfunction "K_2") (pintype "passive"))
      (node (ref "P26") (pin "2") (pinfunction "2_2") (pintype "passive"))
      (node (ref "Q8") (pin "1") (pinfunction "G_1") (pintype "passive"))
      (node (ref "R8") (pin "1") (pinfunction "1_1") (pintype "passive"))
    )
    (net (code "32") (name "Net-(D23-A)") (class "Default")
      (node (ref "D23") (pin "1") (pinfunction "A_1") (pintype "passive"))
      (node (ref "R67") (pin "1") (pinfunction "1_1") (pintype "passive"))
    )
    (net (code "33") (name "Net-(D23-K)") (class "Default")
      (node (ref "D23") (pin "2") (pinfunction "K_2") (pintype "passive"))
      (node (ref "P13") (pin "1") (pinfunction "1_1") (pintype "passive"))
      (node (ref "Q16") (pin "1") (pinfunction "G_1") (pintype "passive"))
      (node (ref "R44") (pin "1") (pinfunction "1_1") (pintype "passive"))
    )
    (net (code "34") (name "Net-(D24-A)") (class "Default")
      (node (ref "D24") (pin "1") (pinfunction "A_1") (pintype "passive"))
      (node (ref "R68") (pin "1") (pinfunction "1_1") (pintype "passive"))
    )
    (net (code "35") (name "Net-(D24-K)") (class "Default")
      (node (ref "D24") (pin "2") (pinfunction "K_2") (pintype "passive"))
      (node (ref "P9") (pin "1") (pinfunction "1_1") (pintype "passive"))
      (node (ref "Q17") (pin "1") (pinfunction "G_1") (pintype "passive"))
      (node (ref "R40") (pin "1") (pinfunction "1_1") (pintype "passive"))
    )
    (net (code "36") (name "Net-(D25-A)") (class "Default")
      (node (ref "D25") (pin "1") (pinfunction "A_1") (pintype "passive"))
      (node (ref "R69") (pin "1") (pinfunction "1_1") (pintype "passive"))
    )
    (net (code "37") (name "Net-(D25-K)") (class "Default")
      (node (ref "D25") (pin "2") (pinfunction "K_2") (pintype "passive"))
      (node (ref "P27") (pin "2") (pinfunction "2_2") (pintype "passive"))
      (node (ref "Q9") (pin "1") (pinfunction "G_1") (pintype "passive"))
      (node (ref "R14") (pin "1") (pinfunction "1_1") (pintype "passive"))
    )
    (net (code "38") (name "Net-(D26-A)") (class "Default")
      (node (ref "D26") (pin "1") (pinfunction "A_1") (pintype "passive"))
      (node (ref "R70") (pin "1") (pinfunction "1_1") (pintype "passive"))
    )
    (net (code "39") (name "Net-(D26-K)") (class "Default")
      (node (ref "D26") (pin "2") (pinfunction "K_2") (pintype "passive"))
      (node (ref "P14") (pin "1") (pinfunction "1_1") (pintype "passive"))
      (node (ref "Q19") (pin "1") (pinfunction "G_1") (pintype "passive"))
      (node (ref "R1") (pin "1") (pinfunction "1_1") (pintype "passive"))
    )
    (net (code "40") (name "Net-(D27-A)") (class "Default")
      (node (ref "D27") (pin "1") (pinfunction "A_1") (pintype "passive"))
      (node (ref "R71") (pin "1") (pinfunction "1_1") (pintype "passive"))
    )
    (net (code "41") (name "Net-(D27-K)") (class "Default")
      (node (ref "D27") (pin "2") (pinfunction "K_2") (pintype "passive"))
      (node (ref "P10") (pin "1") (pinfunction "1_1") (pintype "passive"))
      (node (ref "Q20") (pin "1") (pinfunction "G_1") (pintype "passive"))
      (node (ref "R41") (pin "1") (pinfunction "1_1") (pintype "passive"))
    )
    (net (code "42") (name "Net-(D28-A)") (class "Default")
      (node (ref "D28") (pin "1") (pinfunction "A_1") (pintype "passive"))
      (node (ref "R72") (pin "1") (pinfunction "1_1") (pintype "passive"))
    )
    (net (code "43") (name "Net-(D28-K)") (class "Default")
      (node (ref "D28") (pin "2") (pinfunction "K_2") (pintype "passive"))
      (node (ref "P28") (pin "2") (pinfunction "2_2") (pintype "passive"))
      (node (ref "Q10") (pin "1") (pinfunction "G_1") (pintype "passive"))
      (node (ref "R16") (pin "1") (pinfunction "1_1") (pintype "passive"))
    )
    (net (code "44") (name "Net-(D29-A)") (class "Default")
      (node (ref "D29") (pin "1") (pinfunction "A_1") (pintype "passive"))
      (node (ref "R73") (pin "1") (pinfunction "1_1") (pintype "passive"))
    )
    (net (code "45") (name "Net-(D29-K)") (class "Default")
      (node (ref "D29") (pin "2") (pinfunction "K_2") (pintype "passive"))
      (node (ref "P15") (pin "1") (pinfunction "1_1") (pintype "passive"))
      (node (ref "Q21") (pin "1") (pinfunction "G_1") (pintype "passive"))
      (node (ref "R2") (pin "1") (pinfunction "1_1") (pintype "passive"))
    )
    (net (code "46") (name "Net-(D30-A)") (class "Default")
      (node (ref "D30") (pin "1") (pinfunction "A_1") (pintype "passive"))
      (node (ref "R74") (pin "1") (pinfunction "1_1") (pintype "passive"))
    )
    (net (code "47") (name "Net-(D30-K)") (class "Default")
      (node (ref "D30") (pin "2") (pinfunction "K_2") (pintype "passive"))
      (node (ref "P11") (pin "1") (pinfunction "1_1") (pintype "passive"))
      (node (ref "Q22") (pin "1") (pinfunction "G_1") (pintype "passive"))
      (node (ref "R42") (pin "1") (pinfunction "1_1") (pintype "passive"))
    )
    (net (code "48") (name "Net-(D31-A)") (class "Default")
      (node (ref "D31") (pin "1") (pinfunction "A_1") (pintype "passive"))
      (node (ref "R75") (pin "1") (pinfunction "1_1") (pintype "passive"))
    )
    (net (code "49") (name "Net-(D31-K)") (class "Default")
      (node (ref "D31") (pin "2") (pinfunction "K_2") (pintype "passive"))
      (node (ref "P29") (pin "2") (pinfunction "2_2") (pintype "passive"))
      (node (ref "Q11") (pin "1") (pinfunction "G_1") (pintype "passive"))
      (node (ref "R18") (pin "1") (pinfunction "1_1") (pintype "passive"))
    )
    (net (code "50") (name "Net-(Q13-G)") (class "Default")
      (node (ref "Q13") (pin "1") (pinfunction "G_1") (pintype "passive"))
      (node (ref "U9") (pin "6") (pinfunction "OUT1_6") (pintype "passive"))
    )
    (net (code "51") (name "Net-(Q18-G)") (class "Default")
      (node (ref "P30") (pin "1") (pinfunction "1_1") (pintype "passive"))
      (node (ref "Q18") (pin "1") (pinfunction "G_1") (pintype "passive"))
      (node (ref "R51") (pin "1") (pinfunction "1_1") (pintype "passive"))
    )
    (net (code "52") (name "Net-(Q23-G)") (class "Default")
      (node (ref "P31") (pin "1") (pinfunction "1_1") (pintype "passive"))
      (node (ref "Q23") (pin "1") (pinfunction "G_1") (pintype "passive"))
      (node (ref "R53") (pin "1") (pinfunction "1_1") (pintype "passive"))
    )
    (net (code "53") (name "Net-(U9-IN1)") (class "Default")
      (node (ref "SW1") (pin "4") (pinfunction "4_4") (pintype "passive"))
      (node (ref "U9") (pin "1") (pinfunction "IN1_1") (pintype "passive"))
    )
    (net (code "54") (name "unconnected-(SW1-Pad1)") (class "Default")
      (node (ref "SW1") (pin "1") (pinfunction "1_1") (pintype "passive"))
    )
    (net (code "55") (name "unconnected-(SW1-Pad2)") (class "Default")
      (node (ref "SW1") (pin "2") (pinfunction "2_2") (pintype "passive"))
    )
    (net (code "56") (name "unconnected-(U9-IN2-Pad3)") (class "Default")
      (node (ref "U9") (pin "3") (pinfunction "IN2_3") (pintype "passive"))
    )
    (net (code "57") (name "unconnected-(U9-OUT2-Pad4)") (class "Default")
      (node (ref "U9") (pin "4") (pinfunction "OUT2_4") (pintype "passive"))
    )
  )
)
